# design.net
KiCad netlist of a schematic drawn in EasyEDA Pro
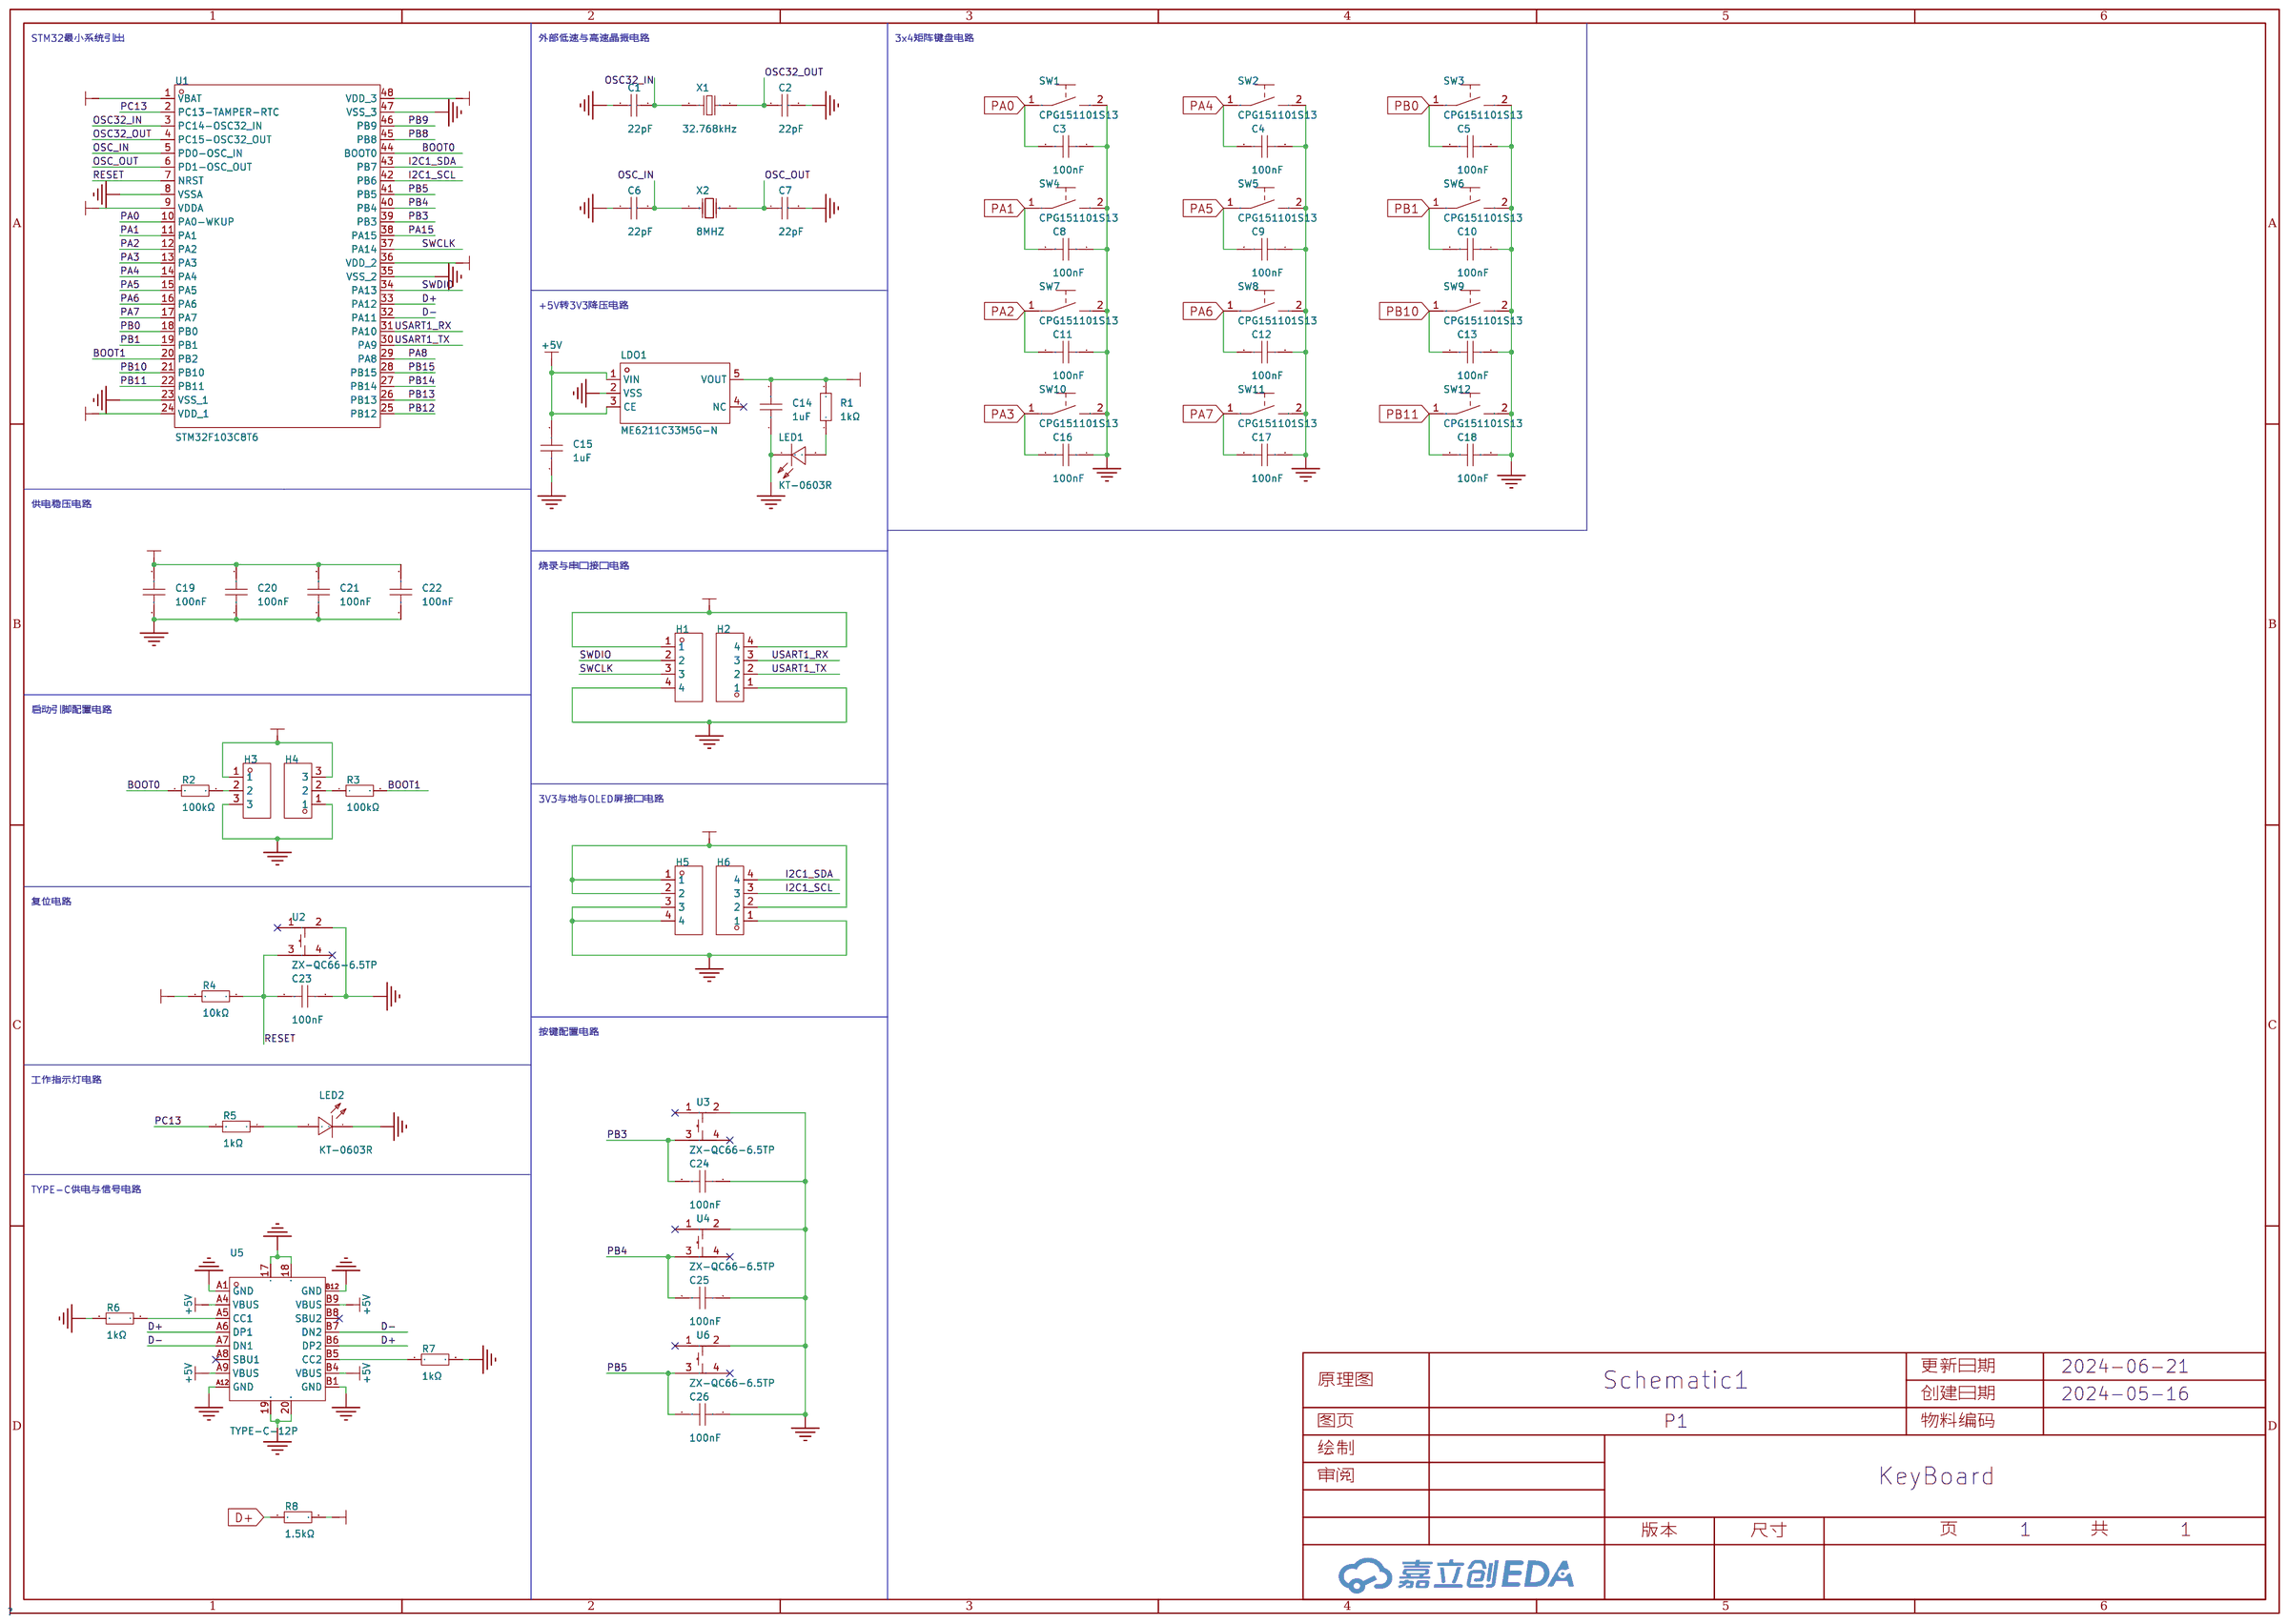
[diagram p0: schematic sheet]

(export (version "E")
  (design (tool "Eeschema 10.0.6"))
  (components
    (comp (ref "C1")
      (value "22pF")
      (footprint "easyedapro:C0603")
      (description "容值:22pF;精度:±5%;额定电压:50V;材质(温度系数):C0G;")
      (fields
        (field (name "Manufacturer Part") "CL10C220JB8NNNC")
        (field (name "Manufacturer") "SAMSUNG(三星)")
      )
      (libsource (lib "easyedapro") (part "CL10C220JB8NNNC"))
    )
    (comp (ref "C2")
      (value "22pF")
      (footprint "easyedapro:C0603")
      (description "容值:22pF;精度:±5%;额定电压:50V;材质(温度系数):C0G;")
      (fields
        (field (name "Manufacturer Part") "CL10C220JB8NNNC")
        (field (name "Manufacturer") "SAMSUNG(三星)")
      )
      (libsource (lib "easyedapro") (part "CL10C220JB8NNNC"))
    )
    (comp (ref "C3")
      (value "100nF")
      (footprint "easyedapro:C0603")
      (description "容值:100nF;精度:±10%;额定电压:50V;材质(温度系数):X7R;")
      (fields
        (field (name "Manufacturer Part") "CC0603KRX7R9BB104")
        (field (name "Manufacturer") "YAGEO(国巨)")
      )
      (libsource (lib "easyedapro") (part "CC0603KRX7R9BB104"))
    )
    (comp (ref "C4")
      (value "100nF")
      (footprint "easyedapro:C0603")
      (description "容值:100nF;精度:±10%;额定电压:50V;材质(温度系数):X7R;")
      (fields
        (field (name "Manufacturer Part") "CC0603KRX7R9BB104")
        (field (name "Manufacturer") "YAGEO(国巨)")
      )
      (libsource (lib "easyedapro") (part "CC0603KRX7R9BB104"))
    )
    (comp (ref "C5")
      (value "100nF")
      (footprint "easyedapro:C0603")
      (description "容值:100nF;精度:±10%;额定电压:50V;材质(温度系数):X7R;")
      (fields
        (field (name "Manufacturer Part") "CC0603KRX7R9BB104")
        (field (name "Manufacturer") "YAGEO(国巨)")
      )
      (libsource (lib "easyedapro") (part "CC0603KRX7R9BB104"))
    )
    (comp (ref "C6")
      (value "22pF")
      (footprint "easyedapro:C0603")
      (description "容值:22pF;精度:±5%;额定电压:50V;材质(温度系数):C0G;")
      (fields
        (field (name "Manufacturer Part") "CL10C220JB8NNNC")
        (field (name "Manufacturer") "SAMSUNG(三星)")
      )
      (libsource (lib "easyedapro") (part "CL10C220JB8NNNC"))
    )
    (comp (ref "C7")
      (value "22pF")
      (footprint "easyedapro:C0603")
      (description "容值:22pF;精度:±5%;额定电压:50V;材质(温度系数):C0G;")
      (fields
        (field (name "Manufacturer Part") "CL10C220JB8NNNC")
        (field (name "Manufacturer") "SAMSUNG(三星)")
      )
      (libsource (lib "easyedapro") (part "CL10C220JB8NNNC"))
    )
    (comp (ref "C8")
      (value "100nF")
      (footprint "easyedapro:C0603")
      (description "容值:100nF;精度:±10%;额定电压:50V;材质(温度系数):X7R;")
      (fields
        (field (name "Manufacturer Part") "CC0603KRX7R9BB104")
        (field (name "Manufacturer") "YAGEO(国巨)")
      )
      (libsource (lib "easyedapro") (part "CC0603KRX7R9BB104"))
    )
    (comp (ref "C9")
      (value "100nF")
      (footprint "easyedapro:C0603")
      (description "容值:100nF;精度:±10%;额定电压:50V;材质(温度系数):X7R;")
      (fields
        (field (name "Manufacturer Part") "CC0603KRX7R9BB104")
        (field (name "Manufacturer") "YAGEO(国巨)")
      )
      (libsource (lib "easyedapro") (part "CC0603KRX7R9BB104"))
    )
    (comp (ref "C10")
      (value "100nF")
      (footprint "easyedapro:C0603")
      (description "容值:100nF;精度:±10%;额定电压:50V;材质(温度系数):X7R;")
      (fields
        (field (name "Manufacturer Part") "CC0603KRX7R9BB104")
        (field (name "Manufacturer") "YAGEO(国巨)")
      )
      (libsource (lib "easyedapro") (part "CC0603KRX7R9BB104"))
    )
    (comp (ref "C11")
      (value "100nF")
      (footprint "easyedapro:C0603")
      (description "容值:100nF;精度:±10%;额定电压:50V;材质(温度系数):X7R;")
      (fields
        (field (name "Manufacturer Part") "CC0603KRX7R9BB104")
        (field (name "Manufacturer") "YAGEO(国巨)")
      )
      (libsource (lib "easyedapro") (part "CC0603KRX7R9BB104"))
    )
    (comp (ref "C12")
      (value "100nF")
      (footprint "easyedapro:C0603")
      (description "容值:100nF;精度:±10%;额定电压:50V;材质(温度系数):X7R;")
      (fields
        (field (name "Manufacturer Part") "CC0603KRX7R9BB104")
        (field (name "Manufacturer") "YAGEO(国巨)")
      )
      (libsource (lib "easyedapro") (part "CC0603KRX7R9BB104"))
    )
    (comp (ref "C13")
      (value "100nF")
      (footprint "easyedapro:C0603")
      (description "容值:100nF;精度:±10%;额定电压:50V;材质(温度系数):X7R;")
      (fields
        (field (name "Manufacturer Part") "CC0603KRX7R9BB104")
        (field (name "Manufacturer") "YAGEO(国巨)")
      )
      (libsource (lib "easyedapro") (part "CC0603KRX7R9BB104"))
    )
    (comp (ref "C14")
      (value "1uF")
      (footprint "easyedapro:C0603")
      (description "容值:1uF;精度:±10%;额定电压:50V;材质(温度系数):X5R;")
      (fields
        (field (name "Manufacturer Part") "CL10A105KB8NNNC")
        (field (name "Manufacturer") "SAMSUNG(三星)")
      )
      (libsource (lib "easyedapro") (part "CL10A105KB8NNNC"))
    )
    (comp (ref "C15")
      (value "1uF")
      (footprint "easyedapro:C0603")
      (description "容值:1uF;精度:±10%;额定电压:50V;材质(温度系数):X5R;")
      (fields
        (field (name "Manufacturer Part") "CL10A105KB8NNNC")
        (field (name "Manufacturer") "SAMSUNG(三星)")
      )
      (libsource (lib "easyedapro") (part "CL10A105KB8NNNC"))
    )
    (comp (ref "C16")
      (value "100nF")
      (footprint "easyedapro:C0603")
      (description "容值:100nF;精度:±10%;额定电压:50V;材质(温度系数):X7R;")
      (fields
        (field (name "Manufacturer Part") "CC0603KRX7R9BB104")
        (field (name "Manufacturer") "YAGEO(国巨)")
      )
      (libsource (lib "easyedapro") (part "CC0603KRX7R9BB104"))
    )
    (comp (ref "C17")
      (value "100nF")
      (footprint "easyedapro:C0603")
      (description "容值:100nF;精度:±10%;额定电压:50V;材质(温度系数):X7R;")
      (fields
        (field (name "Manufacturer Part") "CC0603KRX7R9BB104")
        (field (name "Manufacturer") "YAGEO(国巨)")
      )
      (libsource (lib "easyedapro") (part "CC0603KRX7R9BB104"))
    )
    (comp (ref "C18")
      (value "100nF")
      (footprint "easyedapro:C0603")
      (description "容值:100nF;精度:±10%;额定电压:50V;材质(温度系数):X7R;")
      (fields
        (field (name "Manufacturer Part") "CC0603KRX7R9BB104")
        (field (name "Manufacturer") "YAGEO(国巨)")
      )
      (libsource (lib "easyedapro") (part "CC0603KRX7R9BB104"))
    )
    (comp (ref "C19")
      (value "100nF")
      (footprint "easyedapro:C0603")
      (description "容值:100nF;精度:±10%;额定电压:50V;材质(温度系数):X7R;")
      (fields
        (field (name "Manufacturer Part") "CC0603KRX7R9BB104")
        (field (name "Manufacturer") "YAGEO(国巨)")
      )
      (libsource (lib "easyedapro") (part "CC0603KRX7R9BB104"))
    )
    (comp (ref "C20")
      (value "100nF")
      (footprint "easyedapro:C0603")
      (description "容值:100nF;精度:±10%;额定电压:50V;材质(温度系数):X7R;")
      (fields
        (field (name "Manufacturer Part") "CC0603KRX7R9BB104")
        (field (name "Manufacturer") "YAGEO(国巨)")
      )
      (libsource (lib "easyedapro") (part "CC0603KRX7R9BB104"))
    )
    (comp (ref "C21")
      (value "100nF")
      (footprint "easyedapro:C0603")
      (description "容值:100nF;精度:±10%;额定电压:50V;材质(温度系数):X7R;")
      (fields
        (field (name "Manufacturer Part") "CC0603KRX7R9BB104")
        (field (name "Manufacturer") "YAGEO(国巨)")
      )
      (libsource (lib "easyedapro") (part "CC0603KRX7R9BB104"))
    )
    (comp (ref "C22")
      (value "100nF")
      (footprint "easyedapro:C0603")
      (description "容值:100nF;精度:±10%;额定电压:50V;材质(温度系数):X7R;")
      (fields
        (field (name "Manufacturer Part") "CC0603KRX7R9BB104")
        (field (name "Manufacturer") "YAGEO(国巨)")
      )
      (libsource (lib "easyedapro") (part "CC0603KRX7R9BB104"))
    )
    (comp (ref "C23")
      (value "100nF")
      (footprint "easyedapro:C0603")
      (description "容值:100nF;精度:±10%;额定电压:50V;材质(温度系数):X7R;")
      (fields
        (field (name "Manufacturer Part") "CC0603KRX7R9BB104")
        (field (name "Manufacturer") "YAGEO(国巨)")
      )
      (libsource (lib "easyedapro") (part "CC0603KRX7R9BB104"))
    )
    (comp (ref "C24")
      (value "100nF")
      (footprint "easyedapro:C0603")
      (description "容值:100nF;精度:±10%;额定电压:50V;材质(温度系数):X7R;")
      (fields
        (field (name "Manufacturer Part") "CC0603KRX7R9BB104")
        (field (name "Manufacturer") "YAGEO(国巨)")
      )
      (libsource (lib "easyedapro") (part "CC0603KRX7R9BB104"))
    )
    (comp (ref "C25")
      (value "100nF")
      (footprint "easyedapro:C0603")
      (description "容值:100nF;精度:±10%;额定电压:50V;材质(温度系数):X7R;")
      (fields
        (field (name "Manufacturer Part") "CC0603KRX7R9BB104")
        (field (name "Manufacturer") "YAGEO(国巨)")
      )
      (libsource (lib "easyedapro") (part "CC0603KRX7R9BB104"))
    )
    (comp (ref "C26")
      (value "100nF")
      (footprint "easyedapro:C0603")
      (description "容值:100nF;精度:±10%;额定电压:50V;材质(温度系数):X7R;")
      (fields
        (field (name "Manufacturer Part") "CC0603KRX7R9BB104")
        (field (name "Manufacturer") "YAGEO(国巨)")
      )
      (libsource (lib "easyedapro") (part "CC0603KRX7R9BB104"))
    )
    (comp (ref "H1")
      (value "~")
      (footprint "easyedapro:HDR-TH_4P-P2.54-V-F")
      (libsource (lib "easyedapro") (part "2.54-1*4P母"))
    )
    (comp (ref "H2")
      (value "~")
      (footprint "easyedapro:HDR-TH_4P-P2.54-V-F")
      (libsource (lib "easyedapro") (part "2.54-1*4P母"))
    )
    (comp (ref "H3")
      (value "~")
      (footprint "easyedapro:HDR-TH_3P-P2.54-V-F")
      (libsource (lib "easyedapro") (part "PM254V-11-03-H85"))
    )
    (comp (ref "H4")
      (value "~")
      (footprint "easyedapro:HDR-TH_3P-P2.54-V-F")
      (libsource (lib "easyedapro") (part "PM254V-11-03-H85"))
    )
    (comp (ref "H5")
      (value "~")
      (footprint "easyedapro:HDR-TH_4P-P2.54-V-F")
      (libsource (lib "easyedapro") (part "2.54-1*4P母"))
    )
    (comp (ref "H6")
      (value "~")
      (footprint "easyedapro:HDR-TH_4P-P2.54-V-F")
      (libsource (lib "easyedapro") (part "2.54-1*4P母"))
    )
    (comp (ref "LDO1")
      (value "ME6211C33M5G-N")
      (footprint "easyedapro:SOT-23-5_L3.0-W1.7-P0.95-LS2.8-BL")
      (description "输出类型:固定;最大输入电压:6V;输出电压:3.3V;最大输出电流:500mA;电源纹波抑制比(PSRR):70dB;输出极性:正极;")
      (fields (field (name "Manufacturer") "MICRONE(南京微盟)"))
      (libsource (lib "easyedapro") (part "ME6211C33M5G-N"))
    )
    (comp (ref "LED1")
      (value "KT-0603R")
      (footprint "easyedapro:LED0603-RD")
      (description "发光颜色:红色;功率:-;正向电流:-;主波长:-;二极管配置:-;透镜颜色:-;色温:-;发光角度:-;载带方式:-;工作温度:-40°C~+85°C;")
      (fields (field (name "Manufacturer") "KENTO"))
      (libsource (lib "easyedapro") (part "KT-0603R"))
    )
    (comp (ref "LED2")
      (value "KT-0603R")
      (footprint "easyedapro:LED0603-RD")
      (description "发光颜色:红色;功率:-;正向电流:-;主波长:-;二极管配置:-;透镜颜色:-;色温:-;发光角度:-;载带方式:-;工作温度:-40°C~+85°C;")
      (fields (field (name "Manufacturer") "KENTO"))
      (libsource (lib "easyedapro") (part "KT-0603R"))
    )
    (comp (ref "R1")
      (value "1kΩ")
      (footprint "easyedapro:R0603")
      (description "电阻类型:厚膜电阻;阻值:1kΩ;精度:±1%;功率:100mW;最大工作电压:75V;温度系数:±100ppm/°C;")
      (fields
        (field (name "Manufacturer Part") "0603WAF1001T5E")
        (field (name "Manufacturer") "UNI-ROYAL(厚声)")
      )
      (libsource (lib "easyedapro") (part "0603WAF1001T5E"))
    )
    (comp (ref "R2")
      (value "100kΩ")
      (footprint "easyedapro:R0603")
      (description "电阻类型:厚膜电阻;阻值:100kΩ;精度:±1%;功率:100mW;最大工作电压:75V;温度系数:±100ppm/°C;")
      (fields
        (field (name "Manufacturer Part") "0603WAF1003T5E")
        (field (name "Manufacturer") "UNI-ROYAL(厚声)")
      )
      (libsource (lib "easyedapro") (part "0603WAF1003T5E"))
    )
    (comp (ref "R3")
      (value "100kΩ")
      (footprint "easyedapro:R0603")
      (description "电阻类型:厚膜电阻;阻值:100kΩ;精度:±1%;功率:100mW;最大工作电压:75V;温度系数:±100ppm/°C;")
      (fields
        (field (name "Manufacturer Part") "0603WAF1003T5E")
        (field (name "Manufacturer") "UNI-ROYAL(厚声)")
      )
      (libsource (lib "easyedapro") (part "0603WAF1003T5E"))
    )
    (comp (ref "R4")
      (value "10kΩ")
      (footprint "easyedapro:R0603")
      (description "电阻类型:厚膜电阻;阻值:10kΩ;精度:±1%;功率:100mW;最大工作电压:75V;温度系数:±100ppm/°C;")
      (fields
        (field (name "Manufacturer Part") "0603WAF1002T5E")
        (field (name "Manufacturer") "UNI-ROYAL(厚声)")
      )
      (libsource (lib "easyedapro") (part "0603WAF1002T5E"))
    )
    (comp (ref "R5")
      (value "1kΩ")
      (footprint "easyedapro:R0603")
      (description "电阻类型:厚膜电阻;阻值:1kΩ;精度:±1%;功率:100mW;最大工作电压:75V;温度系数:±100ppm/°C;")
      (fields
        (field (name "Manufacturer Part") "0603WAF1001T5E")
        (field (name "Manufacturer") "UNI-ROYAL(厚声)")
      )
      (libsource (lib "easyedapro") (part "0603WAF1001T5E"))
    )
    (comp (ref "R6")
      (value "1kΩ")
      (footprint "easyedapro:R0603")
      (description "电阻类型:厚膜电阻;阻值:10kΩ;精度:±1%;功率:100mW;最大工作电压:75V;温度系数:±100ppm/°C;")
      (fields
        (field (name "Manufacturer Part") "0603WAF1002T5E")
        (field (name "Manufacturer") "UNI-ROYAL(厚声)")
      )
      (libsource (lib "easyedapro") (part "0603WAF1002T5E"))
    )
    (comp (ref "R7")
      (value "1kΩ")
      (footprint "easyedapro:R0603")
      (description "电阻类型:厚膜电阻;阻值:10kΩ;精度:±1%;功率:100mW;最大工作电压:75V;温度系数:±100ppm/°C;")
      (fields
        (field (name "Manufacturer Part") "0603WAF1002T5E")
        (field (name "Manufacturer") "UNI-ROYAL(厚声)")
      )
      (libsource (lib "easyedapro") (part "0603WAF1002T5E"))
    )
    (comp (ref "R8")
      (value "1.5kΩ")
      (footprint "easyedapro:R0603")
      (description "电阻类型:厚膜电阻;阻值:1.5kΩ;精度:±1%;功率:100mW;最大工作电压:75V;温度系数:±100ppm/°C;")
      (fields
        (field (name "Manufacturer Part") "0603WAF1501T5E")
        (field (name "Manufacturer") "UNI-ROYAL(厚声)")
      )
      (libsource (lib "easyedapro") (part "0603WAF1501T5E"))
    )
    (comp (ref "SW1")
      (value "CPG151101S13")
      (footprint "easyedapro:KEY-TH_CPG1511F01S0X")
      (description "轴类型:青轴;工作电压:2V~12V;针脚数:2;操作力:50gf@±10gf;")
      (fields (field (name "Manufacturer") "Kailh(凯华)"))
      (libsource (lib "easyedapro") (part "CPG151101S13"))
    )
    (comp (ref "SW2")
      (value "CPG151101S13")
      (footprint "easyedapro:KEY-TH_CPG1511F01S0X")
      (description "轴类型:青轴;工作电压:2V~12V;针脚数:2;操作力:50gf@±10gf;")
      (fields (field (name "Manufacturer") "Kailh(凯华)"))
      (libsource (lib "easyedapro") (part "CPG151101S13"))
    )
    (comp (ref "SW3")
      (value "CPG151101S13")
      (footprint "easyedapro:KEY-TH_CPG1511F01S0X")
      (description "轴类型:青轴;工作电压:2V~12V;针脚数:2;操作力:50gf@±10gf;")
      (fields (field (name "Manufacturer") "Kailh(凯华)"))
      (libsource (lib "easyedapro") (part "CPG151101S13"))
    )
    (comp (ref "SW4")
      (value "CPG151101S13")
      (footprint "easyedapro:KEY-TH_CPG1511F01S0X")
      (description "轴类型:青轴;工作电压:2V~12V;针脚数:2;操作力:50gf@±10gf;")
      (fields (field (name "Manufacturer") "Kailh(凯华)"))
      (libsource (lib "easyedapro") (part "CPG151101S13"))
    )
    (comp (ref "SW5")
      (value "CPG151101S13")
      (footprint "easyedapro:KEY-TH_CPG1511F01S0X")
      (description "轴类型:青轴;工作电压:2V~12V;针脚数:2;操作力:50gf@±10gf;")
      (fields (field (name "Manufacturer") "Kailh(凯华)"))
      (libsource (lib "easyedapro") (part "CPG151101S13"))
    )
    (comp (ref "SW6")
      (value "CPG151101S13")
      (footprint "easyedapro:KEY-TH_CPG1511F01S0X")
      (description "轴类型:青轴;工作电压:2V~12V;针脚数:2;操作力:50gf@±10gf;")
      (fields (field (name "Manufacturer") "Kailh(凯华)"))
      (libsource (lib "easyedapro") (part "CPG151101S13"))
    )
    (comp (ref "SW7")
      (value "CPG151101S13")
      (footprint "easyedapro:KEY-TH_CPG1511F01S0X")
      (description "轴类型:青轴;工作电压:2V~12V;针脚数:2;操作力:50gf@±10gf;")
      (fields (field (name "Manufacturer") "Kailh(凯华)"))
      (libsource (lib "easyedapro") (part "CPG151101S13"))
    )
    (comp (ref "SW8")
      (value "CPG151101S13")
      (footprint "easyedapro:KEY-TH_CPG1511F01S0X")
      (description "轴类型:青轴;工作电压:2V~12V;针脚数:2;操作力:50gf@±10gf;")
      (fields (field (name "Manufacturer") "Kailh(凯华)"))
      (libsource (lib "easyedapro") (part "CPG151101S13"))
    )
    (comp (ref "SW9")
      (value "CPG151101S13")
      (footprint "easyedapro:KEY-TH_CPG1511F01S0X")
      (description "轴类型:青轴;工作电压:2V~12V;针脚数:2;操作力:50gf@±10gf;")
      (fields (field (name "Manufacturer") "Kailh(凯华)"))
      (libsource (lib "easyedapro") (part "CPG151101S13"))
    )
    (comp (ref "SW10")
      (value "CPG151101S13")
      (footprint "easyedapro:KEY-TH_CPG1511F01S0X")
      (description "轴类型:青轴;工作电压:2V~12V;针脚数:2;操作力:50gf@±10gf;")
      (fields (field (name "Manufacturer") "Kailh(凯华)"))
      (libsource (lib "easyedapro") (part "CPG151101S13"))
    )
    (comp (ref "SW11")
      (value "CPG151101S13")
      (footprint "easyedapro:KEY-TH_CPG1511F01S0X")
      (description "轴类型:青轴;工作电压:2V~12V;针脚数:2;操作力:50gf@±10gf;")
      (fields (field (name "Manufacturer") "Kailh(凯华)"))
      (libsource (lib "easyedapro") (part "CPG151101S13"))
    )
    (comp (ref "SW12")
      (value "CPG151101S13")
      (footprint "easyedapro:KEY-TH_CPG1511F01S0X")
      (description "轴类型:青轴;工作电压:2V~12V;针脚数:2;操作力:50gf@±10gf;")
      (fields (field (name "Manufacturer") "Kailh(凯华)"))
      (libsource (lib "easyedapro") (part "CPG151101S13"))
    )
    (comp (ref "U1")
      (value "STM32F103C8T6")
      (footprint "easyedapro:LQFP-48_L7.0-W7.0-P0.50-LS9.0-BL")
      (description "CPU内核:ARM-M3;程序存储容量:64KB;RAM总容量:20KB;GPIO端口数量:37;工作电压范围:2V~3.6V;CPU最大主频:72MHz;程序存储器类型:FLASH;")
      (fields (field (name "Manufacturer") "ST(意法半导体)"))
      (libsource (lib "easyedapro") (part "STM32F103C8T6"))
    )
    (comp (ref "U2")
      (value "ZX-QC66-6.5TP")
      (footprint "easyedapro:KEY-SMD_4P-L6.0-W6.0-P4.50-LS8.6")
      (fields (field (name "Manufacturer") "Megastar(兆星)"))
      (libsource (lib "easyedapro") (part "ZX-QC66-6.5TP"))
    )
    (comp (ref "U3")
      (value "ZX-QC66-6.5TP")
      (footprint "easyedapro:KEY-SMD_4P-L6.0-W6.0-P4.50-LS8.6")
      (fields (field (name "Manufacturer") "Megastar(兆星)"))
      (libsource (lib "easyedapro") (part "ZX-QC66-6.5TP"))
    )
    (comp (ref "U4")
      (value "ZX-QC66-6.5TP")
      (footprint "easyedapro:KEY-SMD_4P-L6.0-W6.0-P4.50-LS8.6")
      (fields (field (name "Manufacturer") "Megastar(兆星)"))
      (libsource (lib "easyedapro") (part "ZX-QC66-6.5TP"))
    )
    (comp (ref "U5")
      (value "TYPE-C-12P")
      (footprint "easyedapro:USB-SMD_TYPE-C16PIN")
      (libsource (lib "easyedapro") (part "TYPE-C-12P"))
    )
    (comp (ref "U6")
      (value "ZX-QC66-6.5TP")
      (footprint "easyedapro:KEY-SMD_4P-L6.0-W6.0-P4.50-LS8.6")
      (fields (field (name "Manufacturer") "Megastar(兆星)"))
      (libsource (lib "easyedapro") (part "ZX-QC66-6.5TP"))
    )
    (comp (ref "X1")
      (value "32.768kHz")
      (footprint "easyedapro:CRYSTAL-SMD_L3.2-W1.5-1")
      (description "晶振类型:贴片晶振;频率:32.768kHz;常温频差:±20ppm;外接负载电容:12.5pF;频率稳定度(全温):±20ppm;")
      (fields
        (field (name "Manufacturer Part") "FC31M2-32.768-NTLLLDT")
        (field (name "Manufacturer") "HCI(杭晶)")
      )
      (libsource (lib "easyedapro") (part "FC31M2-32.768-NTLLLDT"))
    )
    (comp (ref "X2")
      (value "8MHZ")
      (footprint "easyedapro:HC-49S_L11.5-W5.0-P4.88")
      (libsource (lib "easyedapro") (part "8MHZ_C9900021358"))
    )
  )
  (nets
    (net (code "1") (name "+5V") (class "Default")
      (node (ref "C15") (pin "2") (pinfunction "2_2") (pintype "unspecified"))
      (node (ref "LDO1") (pin "1") (pinfunction "VIN_1") (pintype "input"))
      (node (ref "LDO1") (pin "3") (pinfunction "CE_3") (pintype "input"))
      (node (ref "U5") (pin "A4") (pinfunction "VBUS_A4") (pintype "unspecified"))
      (node (ref "U5") (pin "A9") (pinfunction "VBUS_A9") (pintype "unspecified"))
      (node (ref "U5") (pin "B4") (pinfunction "VBUS_B4") (pintype "unspecified"))
      (node (ref "U5") (pin "B9") (pinfunction "VBUS_B9") (pintype "unspecified"))
    )
    (net (code "2") (name "/BOOT0") (class "Default")
      (node (ref "R2") (pin "1") (pinfunction "1_1") (pintype "input"))
      (node (ref "U1") (pin "44") (pinfunction "BOOT0_44") (pintype "unspecified"))
    )
    (net (code "3") (name "/BOOT1") (class "Default")
      (node (ref "R3") (pin "2") (pinfunction "2_2") (pintype "input"))
      (node (ref "U1") (pin "20") (pinfunction "PB2_20") (pintype "unspecified"))
    )
    (net (code "4") (name "/D-") (class "Default")
      (node (ref "U1") (pin "32") (pinfunction "PA11_32") (pintype "unspecified"))
      (node (ref "U5") (pin "A7") (pinfunction "DN1_A7") (pintype "unspecified"))
      (node (ref "U5") (pin "B7") (pinfunction "DN2_B7") (pintype "unspecified"))
    )
    (net (code "5") (name "/I2C1_SCL") (class "Default")
      (node (ref "H6") (pin "3") (pinfunction "3_3") (pintype "unspecified"))
      (node (ref "U1") (pin "42") (pinfunction "PB6_42") (pintype "unspecified"))
    )
    (net (code "6") (name "/I2C1_SDA") (class "Default")
      (node (ref "H6") (pin "4") (pinfunction "4_4") (pintype "unspecified"))
      (node (ref "U1") (pin "43") (pinfunction "PB7_43") (pintype "unspecified"))
    )
    (net (code "7") (name "/OSC32_IN") (class "Default")
      (node (ref "C1") (pin "2") (pinfunction "2_2") (pintype "input"))
      (node (ref "U1") (pin "3") (pinfunction "PC14-OSC32_IN_3") (pintype "unspecified"))
      (node (ref "X1") (pin "2") (pinfunction "2_2") (pintype "unspecified"))
    )
    (net (code "8") (name "/OSC32_OUT") (class "Default")
      (node (ref "C2") (pin "2") (pinfunction "2_2") (pintype "input"))
      (node (ref "U1") (pin "4") (pinfunction "PC15-OSC32_OUT_4") (pintype "unspecified"))
      (node (ref "X1") (pin "1") (pinfunction "1_1") (pintype "unspecified"))
    )
    (net (code "9") (name "/OSC_IN") (class "Default")
      (node (ref "C6") (pin "2") (pinfunction "2_2") (pintype "input"))
      (node (ref "U1") (pin "5") (pinfunction "PD0-OSC_IN_5") (pintype "unspecified"))
      (node (ref "X2") (pin "1") (pinfunction "OSC1_1") (pintype "input"))
    )
    (net (code "10") (name "/OSC_OUT") (class "Default")
      (node (ref "C7") (pin "1") (pinfunction "1_1") (pintype "input"))
      (node (ref "U1") (pin "6") (pinfunction "PD1-OSC_OUT_6") (pintype "unspecified"))
      (node (ref "X2") (pin "2") (pinfunction "OSC2_2") (pintype "input"))
    )
    (net (code "11") (name "/PA8") (class "Default")
      (node (ref "U1") (pin "29") (pinfunction "PA8_29") (pintype "unspecified"))
    )
    (net (code "12") (name "/PA15") (class "Default")
      (node (ref "U1") (pin "38") (pinfunction "PA15_38") (pintype "unspecified"))
    )
    (net (code "13") (name "/PB3") (class "Default")
      (node (ref "C24") (pin "2") (pinfunction "2_2") (pintype "unspecified"))
      (node (ref "U1") (pin "39") (pinfunction "PB3_39") (pintype "unspecified"))
      (node (ref "U3") (pin "3") (pinfunction "3_3") (pintype "unspecified"))
    )
    (net (code "14") (name "/PB4") (class "Default")
      (node (ref "C25") (pin "2") (pinfunction "2_2") (pintype "unspecified"))
      (node (ref "U1") (pin "40") (pinfunction "PB4_40") (pintype "unspecified"))
      (node (ref "U4") (pin "3") (pinfunction "3_3") (pintype "unspecified"))
    )
    (net (code "15") (name "/PB5") (class "Default")
      (node (ref "C26") (pin "2") (pinfunction "2_2") (pintype "unspecified"))
      (node (ref "U1") (pin "41") (pinfunction "PB5_41") (pintype "unspecified"))
      (node (ref "U6") (pin "3") (pinfunction "3_3") (pintype "unspecified"))
    )
    (net (code "16") (name "/PB8") (class "Default")
      (node (ref "U1") (pin "45") (pinfunction "PB8_45") (pintype "unspecified"))
    )
    (net (code "17") (name "/PB9") (class "Default")
      (node (ref "U1") (pin "46") (pinfunction "PB9_46") (pintype "unspecified"))
    )
    (net (code "18") (name "/PB12") (class "Default")
      (node (ref "U1") (pin "25") (pinfunction "PB12_25") (pintype "unspecified"))
    )
    (net (code "19") (name "/PB13") (class "Default")
      (node (ref "U1") (pin "26") (pinfunction "PB13_26") (pintype "unspecified"))
    )
    (net (code "20") (name "/PB14") (class "Default")
      (node (ref "U1") (pin "27") (pinfunction "PB14_27") (pintype "unspecified"))
    )
    (net (code "21") (name "/PB15") (class "Default")
      (node (ref "U1") (pin "28") (pinfunction "PB15_28") (pintype "unspecified"))
    )
    (net (code "22") (name "/PC13") (class "Default")
      (node (ref "R5") (pin "2") (pinfunction "2_2") (pintype "input"))
      (node (ref "U1") (pin "2") (pinfunction "PC13-TAMPER-RTC_2") (pintype "unspecified"))
    )
    (net (code "23") (name "/RESET") (class "Default")
      (node (ref "C23") (pin "2") (pinfunction "2_2") (pintype "unspecified"))
      (node (ref "R4") (pin "1") (pinfunction "1_1") (pintype "input"))
      (node (ref "U1") (pin "7") (pinfunction "NRST_7") (pintype "unspecified"))
      (node (ref "U2") (pin "3") (pinfunction "3_3") (pintype "unspecified"))
    )
    (net (code "24") (name "/SWCLK") (class "Default")
      (node (ref "H1") (pin "3") (pinfunction "3_3") (pintype "unspecified"))
      (node (ref "U1") (pin "37") (pinfunction "PA14_37") (pintype "unspecified"))
    )
    (net (code "25") (name "/SWDIO") (class "Default")
      (node (ref "H1") (pin "2") (pinfunction "2_2") (pintype "unspecified"))
      (node (ref "U1") (pin "34") (pinfunction "PA13_34") (pintype "unspecified"))
    )
    (net (code "26") (name "/USART1_RX") (class "Default")
      (node (ref "H2") (pin "3") (pinfunction "3_3") (pintype "unspecified"))
      (node (ref "U1") (pin "31") (pinfunction "PA10_31") (pintype "unspecified"))
    )
    (net (code "27") (name "/USART1_TX") (class "Default")
      (node (ref "H2") (pin "2") (pinfunction "2_2") (pintype "unspecified"))
      (node (ref "U1") (pin "30") (pinfunction "PA9_30") (pintype "unspecified"))
    )
    (net (code "28") (name "3V3") (class "Default")
      (node (ref "C14") (pin "2") (pinfunction "2_2") (pintype "unspecified"))
      (node (ref "C19") (pin "2") (pinfunction "2_2") (pintype "unspecified"))
      (node (ref "C20") (pin "2") (pinfunction "2_2") (pintype "unspecified"))
      (node (ref "C21") (pin "2") (pinfunction "2_2") (pintype "unspecified"))
      (node (ref "C22") (pin "2") (pinfunction "2_2") (pintype "unspecified"))
      (node (ref "H1") (pin "1") (pinfunction "1_1") (pintype "unspecified"))
      (node (ref "H2") (pin "4") (pinfunction "4_4") (pintype "unspecified"))
      (node (ref "H3") (pin "1") (pinfunction "1_1") (pintype "unspecified"))
      (node (ref "H4") (pin "3") (pinfunction "3_3") (pintype "unspecified"))
      (node (ref "H5") (pin "1") (pinfunction "1_1") (pintype "unspecified"))
      (node (ref "H5") (pin "2") (pinfunction "2_2") (pintype "unspecified"))
      (node (ref "H6") (pin "2") (pinfunction "2_2") (pintype "unspecified"))
      (node (ref "LDO1") (pin "5") (pinfunction "VOUT_5") (pintype "input"))
      (node (ref "R1") (pin "2") (pinfunction "2_2") (pintype "input"))
      (node (ref "R4") (pin "2") (pinfunction "2_2") (pintype "input"))
      (node (ref "R8") (pin "2") (pinfunction "2_2") (pintype "input"))
      (node (ref "U1") (pin "1") (pinfunction "VBAT_1") (pintype "unspecified"))
      (node (ref "U1") (pin "24") (pinfunction "VDD_1_24") (pintype "unspecified"))
      (node (ref "U1") (pin "36") (pinfunction "VDD_2_36") (pintype "unspecified"))
      (node (ref "U1") (pin "48") (pinfunction "VDD_3_48") (pintype "unspecified"))
      (node (ref "U1") (pin "9") (pinfunction "VDDA_9") (pintype "unspecified"))
    )
    (net (code "29") (name "D+") (class "Default")
      (node (ref "R8") (pin "1") (pinfunction "1_1") (pintype "input"))
      (node (ref "U1") (pin "33") (pinfunction "PA12_33") (pintype "unspecified"))
      (node (ref "U5") (pin "A6") (pinfunction "DP1_A6") (pintype "unspecified"))
      (node (ref "U5") (pin "B6") (pinfunction "DP2_B6") (pintype "unspecified"))
    )
    (net (code "30") (name "GND") (class "Default")
      (node (ref "C1") (pin "1") (pinfunction "1_1") (pintype "input"))
      (node (ref "C10") (pin "1") (pinfunction "1_1") (pintype "unspecified"))
      (node (ref "C11") (pin "1") (pinfunction "1_1") (pintype "unspecified"))
      (node (ref "C12") (pin "1") (pinfunction "1_1") (pintype "unspecified"))
      (node (ref "C13") (pin "1") (pinfunction "1_1") (pintype "unspecified"))
      (node (ref "C14") (pin "1") (pinfunction "1_1") (pintype "unspecified"))
      (node (ref "C15") (pin "1") (pinfunction "1_1") (pintype "unspecified"))
      (node (ref "C16") (pin "1") (pinfunction "1_1") (pintype "unspecified"))
      (node (ref "C17") (pin "1") (pinfunction "1_1") (pintype "unspecified"))
      (node (ref "C18") (pin "1") (pinfunction "1_1") (pintype "unspecified"))
      (node (ref "C19") (pin "1") (pinfunction "1_1") (pintype "unspecified"))
      (node (ref "C2") (pin "1") (pinfunction "1_1") (pintype "input"))
      (node (ref "C20") (pin "1") (pinfunction "1_1") (pintype "unspecified"))
      (node (ref "C21") (pin "1") (pinfunction "1_1") (pintype "unspecified"))
      (node (ref "C22") (pin "1") (pinfunction "1_1") (pintype "unspecified"))
      (node (ref "C23") (pin "1") (pinfunction "1_1") (pintype "unspecified"))
      (node (ref "C24") (pin "1") (pinfunction "1_1") (pintype "unspecified"))
      (node (ref "C25") (pin "1") (pinfunction "1_1") (pintype "unspecified"))
      (node (ref "C26") (pin "1") (pinfunction "1_1") (pintype "unspecified"))
      (node (ref "C3") (pin "1") (pinfunction "1_1") (pintype "unspecified"))
      (node (ref "C4") (pin "1") (pinfunction "1_1") (pintype "unspecified"))
      (node (ref "C5") (pin "1") (pinfunction "1_1") (pintype "unspecified"))
      (node (ref "C6") (pin "1") (pinfunction "1_1") (pintype "input"))
      (node (ref "C7") (pin "2") (pinfunction "2_2") (pintype "input"))
      (node (ref "C8") (pin "1") (pinfunction "1_1") (pintype "unspecified"))
      (node (ref "C9") (pin "1") (pinfunction "1_1") (pintype "unspecified"))
      (node (ref "H1") (pin "4") (pinfunction "4_4") (pintype "unspecified"))
      (node (ref "H2") (pin "1") (pinfunction "1_1") (pintype "unspecified"))
      (node (ref "H3") (pin "3") (pinfunction "3_3") (pintype "unspecified"))
      (node (ref "H4") (pin "1") (pinfunction "1_1") (pintype "unspecified"))
      (node (ref "H5") (pin "3") (pinfunction "3_3") (pintype "unspecified"))
      (node (ref "H5") (pin "4") (pinfunction "4_4") (pintype "unspecified"))
      (node (ref "H6") (pin "1") (pinfunction "1_1") (pintype "unspecified"))
      (node (ref "LDO1") (pin "2") (pinfunction "VSS_2") (pintype "input"))
      (node (ref "LED1") (pin "1") (pinfunction "K_1") (pintype "input"))
      (node (ref "LED2") (pin "1") (pinfunction "K_1") (pintype "input"))
      (node (ref "R6") (pin "2") (pinfunction "2_2") (pintype "input"))
      (node (ref "R7") (pin "2") (pinfunction "2_2") (pintype "input"))
      (node (ref "SW1") (pin "2") (pinfunction "2_2") (pintype "unspecified"))
      (node (ref "SW10") (pin "2") (pinfunction "2_2") (pintype "unspecified"))
      (node (ref "SW11") (pin "2") (pinfunction "2_2") (pintype "unspecified"))
      (node (ref "SW12") (pin "2") (pinfunction "2_2") (pintype "unspecified"))
      (node (ref "SW2") (pin "2") (pinfunction "2_2") (pintype "unspecified"))
      (node (ref "SW3") (pin "2") (pinfunction "2_2") (pintype "unspecified"))
      (node (ref "SW4") (pin "2") (pinfunction "2_2") (pintype "unspecified"))
      (node (ref "SW5") (pin "2") (pinfunction "2_2") (pintype "unspecified"))
      (node (ref "SW6") (pin "2") (pinfunction "2_2") (pintype "unspecified"))
      (node (ref "SW7") (pin "2") (pinfunction "2_2") (pintype "unspecified"))
      (node (ref "SW8") (pin "2") (pinfunction "2_2") (pintype "unspecified"))
      (node (ref "SW9") (pin "2") (pinfunction "2_2") (pintype "unspecified"))
      (node (ref "U1") (pin "23") (pinfunction "VSS_1_23") (pintype "unspecified"))
      (node (ref "U1") (pin "35") (pinfunction "VSS_2_35") (pintype "unspecified"))
      (node (ref "U1") (pin "47") (pinfunction "VSS_3_47") (pintype "unspecified"))
      (node (ref "U1") (pin "8") (pinfunction "VSSA_8") (pintype "unspecified"))
      (node (ref "U2") (pin "2") (pinfunction "2_2") (pintype "unspecified"))
      (node (ref "U3") (pin "2") (pinfunction "2_2") (pintype "unspecified"))
      (node (ref "U4") (pin "2") (pinfunction "2_2") (pintype "unspecified"))
      (node (ref "U5") (pin "17") (pinfunction "17_17") (pintype "unspecified"))
      (node (ref "U5") (pin "18") (pinfunction "18_18") (pintype "unspecified"))
      (node (ref "U5") (pin "19") (pinfunction "19_19") (pintype "unspecified"))
      (node (ref "U5") (pin "20") (pinfunction "20_20") (pintype "unspecified"))
      (node (ref "U5") (pin "A1") (pinfunction "GND_A1") (pintype "unspecified"))
      (node (ref "U5") (pin "A12") (pinfunction "GND_A12") (pintype "unspecified"))
      (node (ref "U5") (pin "B1") (pinfunction "GND_B1") (pintype "unspecified"))
      (node (ref "U5") (pin "B12") (pinfunction "GND_B12") (pintype "unspecified"))
      (node (ref "U6") (pin "2") (pinfunction "2_2") (pintype "unspecified"))
    )
    (net (code "31") (name "Net-(H3-Pad2)") (class "Default")
      (node (ref "H3") (pin "2") (pinfunction "2_2") (pintype "unspecified"))
      (node (ref "R2") (pin "2") (pinfunction "2_2") (pintype "input"))
    )
    (net (code "32") (name "Net-(H4-Pad2)") (class "Default")
      (node (ref "H4") (pin "2") (pinfunction "2_2") (pintype "unspecified"))
      (node (ref "R3") (pin "1") (pinfunction "1_1") (pintype "input"))
    )
    (net (code "33") (name "Net-(LED1-A)") (class "Default")
      (node (ref "LED1") (pin "2") (pinfunction "A_2") (pintype "input"))
      (node (ref "R1") (pin "1") (pinfunction "1_1") (pintype "input"))
    )
    (net (code "34") (name "Net-(LED2-A)") (class "Default")
      (node (ref "LED2") (pin "2") (pinfunction "A_2") (pintype "input"))
      (node (ref "R5") (pin "1") (pinfunction "1_1") (pintype "input"))
    )
    (net (code "35") (name "Net-(U5-CC1)") (class "Default")
      (node (ref "R6") (pin "1") (pinfunction "1_1") (pintype "input"))
      (node (ref "U5") (pin "A5") (pinfunction "CC1_A5") (pintype "unspecified"))
    )
    (net (code "36") (name "Net-(U5-CC2)") (class "Default")
      (node (ref "R7") (pin "1") (pinfunction "1_1") (pintype "input"))
      (node (ref "U5") (pin "B5") (pinfunction "CC2_B5") (pintype "unspecified"))
    )
    (net (code "37") (name "PA0") (class "Default")
      (node (ref "C3") (pin "2") (pinfunction "2_2") (pintype "unspecified"))
      (node (ref "SW1") (pin "1") (pinfunction "1_1") (pintype "unspecified"))
      (node (ref "U1") (pin "10") (pinfunction "PA0-WKUP_10") (pintype "unspecified"))
    )
    (net (code "38") (name "PA1") (class "Default")
      (node (ref "C8") (pin "2") (pinfunction "2_2") (pintype "unspecified"))
      (node (ref "SW4") (pin "1") (pinfunction "1_1") (pintype "unspecified"))
      (node (ref "U1") (pin "11") (pinfunction "PA1_11") (pintype "unspecified"))
    )
    (net (code "39") (name "PA2") (class "Default")
      (node (ref "C11") (pin "2") (pinfunction "2_2") (pintype "unspecified"))
      (node (ref "SW7") (pin "1") (pinfunction "1_1") (pintype "unspecified"))
      (node (ref "U1") (pin "12") (pinfunction "PA2_12") (pintype "unspecified"))
    )
    (net (code "40") (name "PA3") (class "Default")
      (node (ref "C16") (pin "2") (pinfunction "2_2") (pintype "unspecified"))
      (node (ref "SW10") (pin "1") (pinfunction "1_1") (pintype "unspecified"))
      (node (ref "U1") (pin "13") (pinfunction "PA3_13") (pintype "unspecified"))
    )
    (net (code "41") (name "PA4") (class "Default")
      (node (ref "C4") (pin "2") (pinfunction "2_2") (pintype "unspecified"))
      (node (ref "SW2") (pin "1") (pinfunction "1_1") (pintype "unspecified"))
      (node (ref "U1") (pin "14") (pinfunction "PA4_14") (pintype "unspecified"))
    )
    (net (code "42") (name "PA5") (class "Default")
      (node (ref "C9") (pin "2") (pinfunction "2_2") (pintype "unspecified"))
      (node (ref "SW5") (pin "1") (pinfunction "1_1") (pintype "unspecified"))
      (node (ref "U1") (pin "15") (pinfunction "PA5_15") (pintype "unspecified"))
    )
    (net (code "43") (name "PA6") (class "Default")
      (node (ref "C12") (pin "2") (pinfunction "2_2") (pintype "unspecified"))
      (node (ref "SW8") (pin "1") (pinfunction "1_1") (pintype "unspecified"))
      (node (ref "U1") (pin "16") (pinfunction "PA6_16") (pintype "unspecified"))
    )
    (net (code "44") (name "PA7") (class "Default")
      (node (ref "C17") (pin "2") (pinfunction "2_2") (pintype "unspecified"))
      (node (ref "SW11") (pin "1") (pinfunction "1_1") (pintype "unspecified"))
      (node (ref "U1") (pin "17") (pinfunction "PA7_17") (pintype "unspecified"))
    )
    (net (code "45") (name "PB0") (class "Default")
      (node (ref "C5") (pin "2") (pinfunction "2_2") (pintype "unspecified"))
      (node (ref "SW3") (pin "1") (pinfunction "1_1") (pintype "unspecified"))
      (node (ref "U1") (pin "18") (pinfunction "PB0_18") (pintype "unspecified"))
    )
    (net (code "46") (name "PB1") (class "Default")
      (node (ref "C10") (pin "2") (pinfunction "2_2") (pintype "unspecified"))
      (node (ref "SW6") (pin "1") (pinfunction "1_1") (pintype "unspecified"))
      (node (ref "U1") (pin "19") (pinfunction "PB1_19") (pintype "unspecified"))
    )
    (net (code "47") (name "PB10") (class "Default")
      (node (ref "C13") (pin "2") (pinfunction "2_2") (pintype "unspecified"))
      (node (ref "SW9") (pin "1") (pinfunction "1_1") (pintype "unspecified"))
      (node (ref "U1") (pin "21") (pinfunction "PB10_21") (pintype "unspecified"))
    )
    (net (code "48") (name "PB11") (class "Default")
      (node (ref "C18") (pin "2") (pinfunction "2_2") (pintype "unspecified"))
      (node (ref "SW12") (pin "1") (pinfunction "1_1") (pintype "unspecified"))
      (node (ref "U1") (pin "22") (pinfunction "PB11_22") (pintype "unspecified"))
    )
    (net (code "49") (name "unconnected-(LDO1-NC-Pad4)") (class "Default")
      (node (ref "LDO1") (pin "4") (pinfunction "NC_4") (pintype "input+no_connect"))
    )
    (net (code "50") (name "unconnected-(U2-Pad1)") (class "Default")
      (node (ref "U2") (pin "1") (pinfunction "1_1") (pintype "unspecified+no_connect"))
    )
    (net (code "51") (name "unconnected-(U2-Pad4)") (class "Default")
      (node (ref "U2") (pin "4") (pinfunction "4_4") (pintype "unspecified+no_connect"))
    )
    (net (code "52") (name "unconnected-(U3-Pad1)") (class "Default")
      (node (ref "U3") (pin "1") (pinfunction "1_1") (pintype "unspecified+no_connect"))
    )
    (net (code "53") (name "unconnected-(U3-Pad4)") (class "Default")
      (node (ref "U3") (pin "4") (pinfunction "4_4") (pintype "unspecified+no_connect"))
    )
    (net (code "54") (name "unconnected-(U4-Pad1)") (class "Default")
      (node (ref "U4") (pin "1") (pinfunction "1_1") (pintype "unspecified+no_connect"))
    )
    (net (code "55") (name "unconnected-(U4-Pad4)") (class "Default")
      (node (ref "U4") (pin "4") (pinfunction "4_4") (pintype "unspecified+no_connect"))
    )
    (net (code "56") (name "unconnected-(U5-SBU1-PadA8)") (class "Default")
      (node (ref "U5") (pin "A8") (pinfunction "SBU1_A8") (pintype "unspecified+no_connect"))
    )
    (net (code "57") (name "unconnected-(U5-SBU2-PadB8)") (class "Default")
      (node (ref "U5") (pin "B8") (pinfunction "SBU2_B8") (pintype "unspecified+no_connect"))
    )
    (net (code "58") (name "unconnected-(U6-Pad1)") (class "Default")
      (node (ref "U6") (pin "1") (pinfunction "1_1") (pintype "unspecified+no_connect"))
    )
    (net (code "59") (name "unconnected-(U6-Pad4)") (class "Default")
      (node (ref "U6") (pin "4") (pinfunction "4_4") (pintype "unspecified+no_connect"))
    )
  )
)
